# Bus-switch.net
KiCad netlist of a schematic drawn in Altium Designer
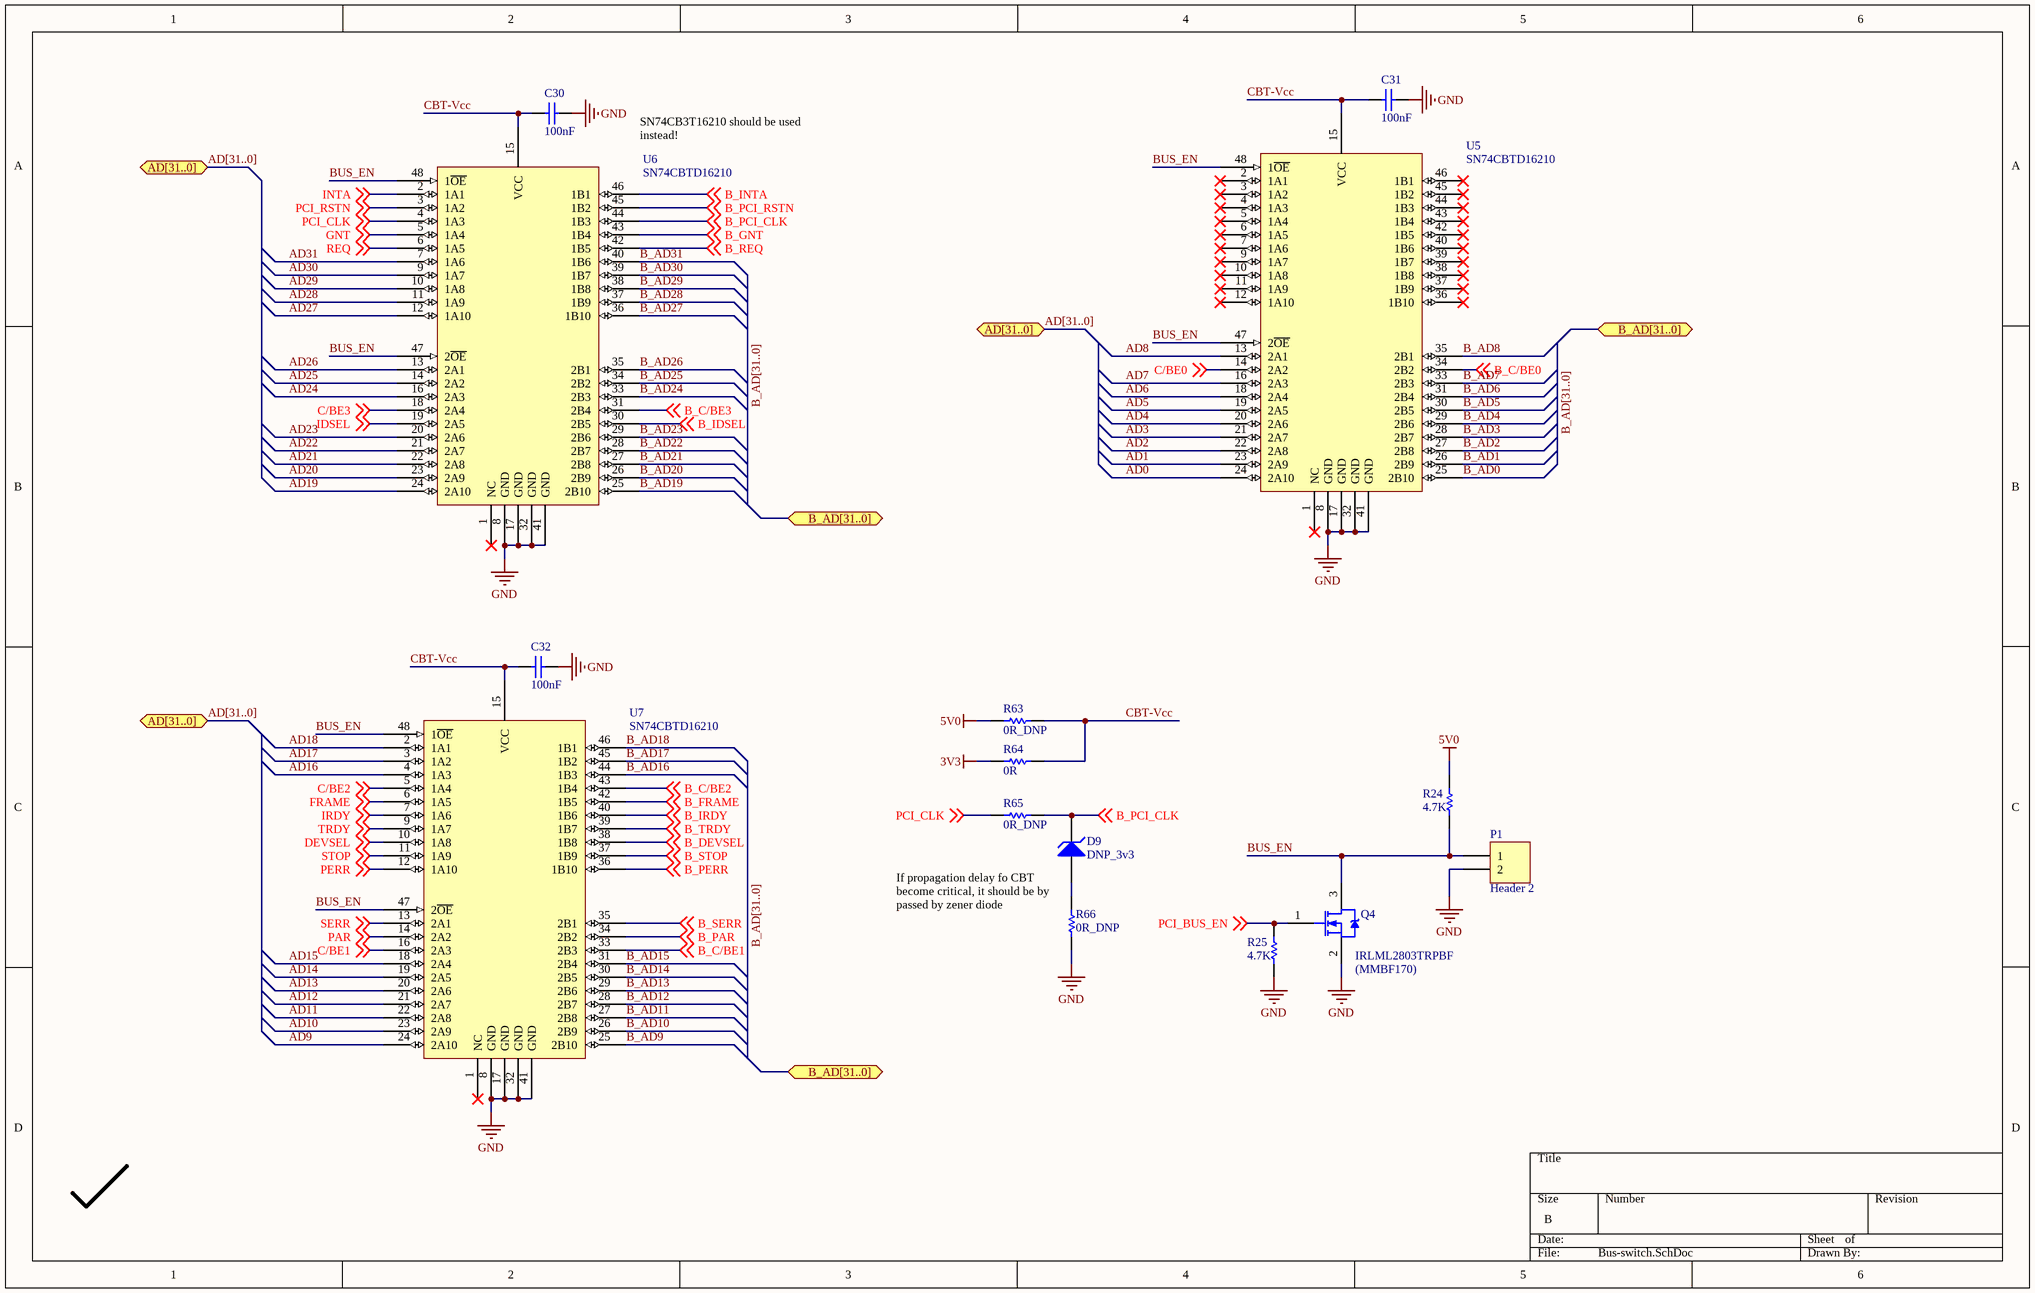
[diagram p0: Bus-switch.SchDoc]

(export (version "E")
  (design (tool "Eeschema 10.0.6"))
  (components
    (comp (ref "C30")
      (value "100nF")
      (footprint "0603PKG")
      (description "Capacitor (Semiconductor SIM Model)")
      (fields (field (name "Comment") "Cap Semi") (field (name "PUBLISHER") "Altium Limited"))
      (libsource (lib "Miscellaneous Devices") (part "Cap Semi"))
    )
    (comp (ref "C31")
      (value "100nF")
      (footprint "0603PKG")
      (description "Capacitor (Semiconductor SIM Model)")
      (fields (field (name "Comment") "Cap Semi") (field (name "PUBLISHER") "Altium Limited"))
      (libsource (lib "Miscellaneous Devices") (part "Cap Semi"))
    )
    (comp (ref "C32")
      (value "100nF")
      (footprint "0603PKG")
      (description "Capacitor (Semiconductor SIM Model)")
      (fields (field (name "Comment") "Cap Semi") (field (name "PUBLISHER") "Altium Limited"))
      (libsource (lib "Miscellaneous Devices") (part "Cap Semi"))
    )
    (comp (ref "D9")
      (value "DNP_3v3")
      (footprint "C1206")
      (description "Zener Diode")
      (fields (field (name "PUBLISHER") "Altium Limited"))
      (libsource (lib "Miscellaneous Devices") (part "D Zener"))
    )
    (comp (ref "P1")
      (value "Header 2")
      (footprint "HDR1X2")
      (description "Header, 2-Pin")
      (fields (field (name "PUBLISHER") "Altium Limited"))
      (libsource (lib "Miscellaneous Connectors") (part "Header 2"))
    )
    (comp (ref "Q4")
      (value "IRLML2803TRPBF")
      (footprint "SOT23")
      (description "N-Channel Power MOSFET")
      (fields (field (name "PUBLISHER") "Altium Limited"))
      (libsource (lib "Miscellaneous Devices") (part "NMOS-2"))
    )
    (comp (ref "R24")
      (value "4.7K")
      (footprint "0603PKG")
      (description "Resistor")
      (fields (field (name "Comment") "Res1") (field (name "PUBLISHER") "Altium Limited"))
      (libsource (lib "Miscellaneous Devices") (part "Res1"))
    )
    (comp (ref "R25")
      (value "4.7K")
      (footprint "0603PKG")
      (description "Resistor")
      (fields (field (name "Comment") "Res1") (field (name "PUBLISHER") "Altium Limited"))
      (libsource (lib "Miscellaneous Devices") (part "Res1"))
    )
    (comp (ref "R63")
      (value "0R_DNP")
      (footprint "0603PKG")
      (description "Resistor")
      (fields (field (name "Comment") "Res1") (field (name "PUBLISHER") "Altium Limited"))
      (libsource (lib "Miscellaneous Devices") (part "Res1"))
    )
    (comp (ref "R64")
      (value "0R")
      (footprint "0603PKG")
      (description "Resistor")
      (fields (field (name "Comment") "Res1") (field (name "PUBLISHER") "Altium Limited"))
      (libsource (lib "Miscellaneous Devices") (part "Res1"))
    )
    (comp (ref "R65")
      (value "0R_DNP")
      (footprint "0603PKG")
      (description "Resistor")
      (fields (field (name "Comment") "Res1") (field (name "PUBLISHER") "Altium Limited"))
      (libsource (lib "Miscellaneous Devices") (part "Res1"))
    )
    (comp (ref "R66")
      (value "0R_DNP")
      (footprint "0603PKG")
      (description "Resistor")
      (fields (field (name "Comment") "Res1") (field (name "PUBLISHER") "Altium Limited"))
      (libsource (lib "Miscellaneous Devices") (part "Res1"))
    )
    (comp (ref "U5")
      (value "SN74CBTD16210")
      (footprint "TSSOP-48-DGG")
      (description "20-BIT FET BUS SWITCH WITH LEVEL SHIFTING")
      (libsource (lib "Conn_Schlib") (part "SN74CBTD16210"))
    )
    (comp (ref "U6")
      (value "SN74CBTD16210")
      (footprint "TSSOP-48-DGG")
      (description "20-BIT FET BUS SWITCH WITH LEVEL SHIFTING")
      (libsource (lib "Conn_Schlib") (part "SN74CBTD16210"))
    )
    (comp (ref "U7")
      (value "SN74CBTD16210")
      (footprint "TSSOP-48-DGG")
      (description "20-BIT FET BUS SWITCH WITH LEVEL SHIFTING")
      (libsource (lib "Conn_Schlib") (part "SN74CBTD16210"))
    )
  )
  (nets
    (net (code "1") (name "/AD0") (class "Default")
      (node (ref "U5") (pin "24") (pinfunction "2A10_24") (pintype "bidirectional"))
    )
    (net (code "2") (name "/AD1") (class "Default")
      (node (ref "U5") (pin "23") (pinfunction "2A9_23") (pintype "bidirectional"))
    )
    (net (code "3") (name "/AD2") (class "Default")
      (node (ref "U5") (pin "22") (pinfunction "2A8_22") (pintype "bidirectional"))
    )
    (net (code "4") (name "/AD3") (class "Default")
      (node (ref "U5") (pin "21") (pinfunction "2A7_21") (pintype "bidirectional"))
    )
    (net (code "5") (name "/AD4") (class "Default")
      (node (ref "U5") (pin "20") (pinfunction "2A6_20") (pintype "bidirectional"))
    )
    (net (code "6") (name "/AD5") (class "Default")
      (node (ref "U5") (pin "19") (pinfunction "2A5_19") (pintype "bidirectional"))
    )
    (net (code "7") (name "/AD6") (class "Default")
      (node (ref "U5") (pin "18") (pinfunction "2A4_18") (pintype "bidirectional"))
    )
    (net (code "8") (name "/AD7") (class "Default")
      (node (ref "U5") (pin "16") (pinfunction "2A3_16") (pintype "bidirectional"))
    )
    (net (code "9") (name "/AD8") (class "Default")
      (node (ref "U5") (pin "13") (pinfunction "2A1_13") (pintype "bidirectional"))
    )
    (net (code "10") (name "/AD9") (class "Default")
      (node (ref "U7") (pin "24") (pinfunction "2A10_24") (pintype "bidirectional"))
    )
    (net (code "11") (name "/AD10") (class "Default")
      (node (ref "U7") (pin "23") (pinfunction "2A9_23") (pintype "bidirectional"))
    )
    (net (code "12") (name "/AD11") (class "Default")
      (node (ref "U7") (pin "22") (pinfunction "2A8_22") (pintype "bidirectional"))
    )
    (net (code "13") (name "/AD12") (class "Default")
      (node (ref "U7") (pin "21") (pinfunction "2A7_21") (pintype "bidirectional"))
    )
    (net (code "14") (name "/AD13") (class "Default")
      (node (ref "U7") (pin "20") (pinfunction "2A6_20") (pintype "bidirectional"))
    )
    (net (code "15") (name "/AD14") (class "Default")
      (node (ref "U7") (pin "19") (pinfunction "2A5_19") (pintype "bidirectional"))
    )
    (net (code "16") (name "/AD15") (class "Default")
      (node (ref "U7") (pin "18") (pinfunction "2A4_18") (pintype "bidirectional"))
    )
    (net (code "17") (name "/AD16") (class "Default")
      (node (ref "U7") (pin "4") (pinfunction "1A3_4") (pintype "bidirectional"))
    )
    (net (code "18") (name "/AD17") (class "Default")
      (node (ref "U7") (pin "3") (pinfunction "1A2_3") (pintype "bidirectional"))
    )
    (net (code "19") (name "/AD18") (class "Default")
      (node (ref "U7") (pin "2") (pinfunction "1A1_2") (pintype "bidirectional"))
    )
    (net (code "20") (name "/AD19") (class "Default")
      (node (ref "U6") (pin "24") (pinfunction "2A10_24") (pintype "bidirectional"))
    )
    (net (code "21") (name "/AD20") (class "Default")
      (node (ref "U6") (pin "23") (pinfunction "2A9_23") (pintype "bidirectional"))
    )
    (net (code "22") (name "/AD21") (class "Default")
      (node (ref "U6") (pin "22") (pinfunction "2A8_22") (pintype "bidirectional"))
    )
    (net (code "23") (name "/AD22") (class "Default")
      (node (ref "U6") (pin "21") (pinfunction "2A7_21") (pintype "bidirectional"))
    )
    (net (code "24") (name "/AD23") (class "Default")
      (node (ref "U6") (pin "20") (pinfunction "2A6_20") (pintype "bidirectional"))
    )
    (net (code "25") (name "/AD24") (class "Default")
      (node (ref "U6") (pin "16") (pinfunction "2A3_16") (pintype "bidirectional"))
    )
    (net (code "26") (name "/AD25") (class "Default")
      (node (ref "U6") (pin "14") (pinfunction "2A2_14") (pintype "bidirectional"))
    )
    (net (code "27") (name "/AD26") (class "Default")
      (node (ref "U6") (pin "13") (pinfunction "2A1_13") (pintype "bidirectional"))
    )
    (net (code "28") (name "/AD27") (class "Default")
      (node (ref "U6") (pin "12") (pinfunction "1A10_12") (pintype "bidirectional"))
    )
    (net (code "29") (name "/AD28") (class "Default")
      (node (ref "U6") (pin "11") (pinfunction "1A9_11") (pintype "bidirectional"))
    )
    (net (code "30") (name "/AD29") (class "Default")
      (node (ref "U6") (pin "10") (pinfunction "1A8_10") (pintype "bidirectional"))
    )
    (net (code "31") (name "/AD30") (class "Default")
      (node (ref "U6") (pin "9") (pinfunction "1A7_9") (pintype "bidirectional"))
    )
    (net (code "32") (name "/AD31") (class "Default")
      (node (ref "U6") (pin "7") (pinfunction "1A6_7") (pintype "bidirectional"))
    )
    (net (code "34") (name "/BUS_EN") (class "Default")
      (node (ref "P1") (pin "1") (pinfunction "1_1") (pintype "passive"))
      (node (ref "Q4") (pin "3") (pinfunction "D_3") (pintype "passive"))
      (node (ref "R24") (pin "1") (pinfunction "1_1") (pintype "passive"))
      (node (ref "U5") (pin "47") (pinfunction "2~{OE}_47") (pintype "input"))
      (node (ref "U5") (pin "48") (pinfunction "1~{OE}_48") (pintype "input"))
      (node (ref "U6") (pin "47") (pinfunction "2~{OE}_47") (pintype "input"))
      (node (ref "U6") (pin "48") (pinfunction "1~{OE}_48") (pintype "input"))
      (node (ref "U7") (pin "47") (pinfunction "2~{OE}_47") (pintype "input"))
      (node (ref "U7") (pin "48") (pinfunction "1~{OE}_48") (pintype "input"))
    )
    (net (code "35") (name "/B_AD0") (class "Default")
      (node (ref "U5") (pin "25") (pinfunction "2B10_25") (pintype "bidirectional"))
    )
    (net (code "36") (name "/B_AD1") (class "Default")
      (node (ref "U5") (pin "26") (pinfunction "2B9_26") (pintype "bidirectional"))
    )
    (net (code "37") (name "/B_AD2") (class "Default")
      (node (ref "U5") (pin "27") (pinfunction "2B8_27") (pintype "bidirectional"))
    )
    (net (code "38") (name "/B_AD3") (class "Default")
      (node (ref "U5") (pin "28") (pinfunction "2B7_28") (pintype "bidirectional"))
    )
    (net (code "39") (name "/B_AD4") (class "Default")
      (node (ref "U5") (pin "29") (pinfunction "2B6_29") (pintype "bidirectional"))
    )
    (net (code "40") (name "/B_AD5") (class "Default")
      (node (ref "U5") (pin "30") (pinfunction "2B5_30") (pintype "bidirectional"))
    )
    (net (code "41") (name "/B_AD6") (class "Default")
      (node (ref "U5") (pin "31") (pinfunction "2B4_31") (pintype "bidirectional"))
    )
    (net (code "42") (name "/B_AD7") (class "Default")
      (node (ref "U5") (pin "33") (pinfunction "2B3_33") (pintype "bidirectional"))
    )
    (net (code "43") (name "/B_AD8") (class "Default")
      (node (ref "U5") (pin "35") (pinfunction "2B1_35") (pintype "bidirectional"))
    )
    (net (code "44") (name "/B_AD9") (class "Default")
      (node (ref "U7") (pin "25") (pinfunction "2B10_25") (pintype "bidirectional"))
    )
    (net (code "45") (name "/B_AD10") (class "Default")
      (node (ref "U7") (pin "26") (pinfunction "2B9_26") (pintype "bidirectional"))
    )
    (net (code "46") (name "/B_AD11") (class "Default")
      (node (ref "U7") (pin "27") (pinfunction "2B8_27") (pintype "bidirectional"))
    )
    (net (code "47") (name "/B_AD12") (class "Default")
      (node (ref "U7") (pin "28") (pinfunction "2B7_28") (pintype "bidirectional"))
    )
    (net (code "48") (name "/B_AD13") (class "Default")
      (node (ref "U7") (pin "29") (pinfunction "2B6_29") (pintype "bidirectional"))
    )
    (net (code "49") (name "/B_AD14") (class "Default")
      (node (ref "U7") (pin "30") (pinfunction "2B5_30") (pintype "bidirectional"))
    )
    (net (code "50") (name "/B_AD15") (class "Default")
      (node (ref "U7") (pin "31") (pinfunction "2B4_31") (pintype "bidirectional"))
    )
    (net (code "51") (name "/B_AD16") (class "Default")
      (node (ref "U7") (pin "44") (pinfunction "1B3_44") (pintype "bidirectional"))
    )
    (net (code "52") (name "/B_AD17") (class "Default")
      (node (ref "U7") (pin "45") (pinfunction "1B2_45") (pintype "bidirectional"))
    )
    (net (code "53") (name "/B_AD18") (class "Default")
      (node (ref "U7") (pin "46") (pinfunction "1B1_46") (pintype "bidirectional"))
    )
    (net (code "54") (name "/B_AD19") (class "Default")
      (node (ref "U6") (pin "25") (pinfunction "2B10_25") (pintype "bidirectional"))
    )
    (net (code "55") (name "/B_AD20") (class "Default")
      (node (ref "U6") (pin "26") (pinfunction "2B9_26") (pintype "bidirectional"))
    )
    (net (code "56") (name "/B_AD21") (class "Default")
      (node (ref "U6") (pin "27") (pinfunction "2B8_27") (pintype "bidirectional"))
    )
    (net (code "57") (name "/B_AD22") (class "Default")
      (node (ref "U6") (pin "28") (pinfunction "2B7_28") (pintype "bidirectional"))
    )
    (net (code "58") (name "/B_AD23") (class "Default")
      (node (ref "U6") (pin "29") (pinfunction "2B6_29") (pintype "bidirectional"))
    )
    (net (code "59") (name "/B_AD24") (class "Default")
      (node (ref "U6") (pin "33") (pinfunction "2B3_33") (pintype "bidirectional"))
    )
    (net (code "60") (name "/B_AD25") (class "Default")
      (node (ref "U6") (pin "34") (pinfunction "2B2_34") (pintype "bidirectional"))
    )
    (net (code "61") (name "/B_AD26") (class "Default")
      (node (ref "U6") (pin "35") (pinfunction "2B1_35") (pintype "bidirectional"))
    )
    (net (code "62") (name "/B_AD27") (class "Default")
      (node (ref "U6") (pin "36") (pinfunction "1B10_36") (pintype "bidirectional"))
    )
    (net (code "63") (name "/B_AD28") (class "Default")
      (node (ref "U6") (pin "37") (pinfunction "1B9_37") (pintype "bidirectional"))
    )
    (net (code "64") (name "/B_AD29") (class "Default")
      (node (ref "U6") (pin "38") (pinfunction "1B8_38") (pintype "bidirectional"))
    )
    (net (code "65") (name "/B_AD30") (class "Default")
      (node (ref "U6") (pin "39") (pinfunction "1B7_39") (pintype "bidirectional"))
    )
    (net (code "66") (name "/B_AD31") (class "Default")
      (node (ref "U6") (pin "40") (pinfunction "1B6_40") (pintype "bidirectional"))
    )
    (net (code "68") (name "/CBT-Vcc") (class "Default")
      (node (ref "C30") (pin "2") (pinfunction "2_2") (pintype "passive"))
      (node (ref "C31") (pin "2") (pinfunction "2_2") (pintype "passive"))
      (node (ref "C32") (pin "2") (pinfunction "2_2") (pintype "passive"))
      (node (ref "R63") (pin "1") (pinfunction "1_1") (pintype "passive"))
      (node (ref "R64") (pin "1") (pinfunction "1_1") (pintype "passive"))
      (node (ref "U5") (pin "15") (pinfunction "VCC_15") (pintype "power_in"))
      (node (ref "U6") (pin "15") (pinfunction "VCC_15") (pintype "power_in"))
      (node (ref "U7") (pin "15") (pinfunction "VCC_15") (pintype "power_in"))
    )
    (net (code "69") (name "3V3") (class "Default")
      (node (ref "R64") (pin "2") (pinfunction "2_2") (pintype "passive"))
    )
    (net (code "70") (name "5V0") (class "Default")
      (node (ref "R24") (pin "2") (pinfunction "2_2") (pintype "passive"))
      (node (ref "R63") (pin "2") (pinfunction "2_2") (pintype "passive"))
    )
    (net (code "71") (name "B_C{slash}BE0") (class "Default")
      (node (ref "U5") (pin "34") (pinfunction "2B2_34") (pintype "bidirectional"))
    )
    (net (code "72") (name "B_C{slash}BE1") (class "Default")
      (node (ref "U7") (pin "33") (pinfunction "2B3_33") (pintype "bidirectional"))
    )
    (net (code "73") (name "B_C{slash}BE2") (class "Default")
      (node (ref "U7") (pin "43") (pinfunction "1B4_43") (pintype "bidirectional"))
    )
    (net (code "74") (name "B_C{slash}BE3") (class "Default")
      (node (ref "U6") (pin "31") (pinfunction "2B4_31") (pintype "bidirectional"))
    )
    (net (code "75") (name "B_DEVSEL") (class "Default")
      (node (ref "U7") (pin "38") (pinfunction "1B8_38") (pintype "bidirectional"))
    )
    (net (code "76") (name "B_FRAME") (class "Default")
      (node (ref "U7") (pin "42") (pinfunction "1B5_42") (pintype "bidirectional"))
    )
    (net (code "77") (name "B_GNT") (class "Default")
      (node (ref "U6") (pin "43") (pinfunction "1B4_43") (pintype "bidirectional"))
    )
    (net (code "78") (name "B_IDSEL") (class "Default")
      (node (ref "U6") (pin "30") (pinfunction "2B5_30") (pintype "bidirectional"))
    )
    (net (code "79") (name "B_INTA") (class "Default")
      (node (ref "U6") (pin "46") (pinfunction "1B1_46") (pintype "bidirectional"))
    )
    (net (code "80") (name "B_IRDY") (class "Default")
      (node (ref "U7") (pin "40") (pinfunction "1B6_40") (pintype "bidirectional"))
    )
    (net (code "81") (name "B_PAR") (class "Default")
      (node (ref "U7") (pin "34") (pinfunction "2B2_34") (pintype "bidirectional"))
    )
    (net (code "82") (name "B_PCI_CLK") (class "Default")
      (node (ref "D9") (pin "2") (pinfunction "K_2") (pintype "passive"))
      (node (ref "R65") (pin "1") (pinfunction "1_1") (pintype "passive"))
      (node (ref "U6") (pin "44") (pinfunction "1B3_44") (pintype "bidirectional"))
    )
    (net (code "83") (name "B_PCI_RSTN") (class "Default")
      (node (ref "U6") (pin "45") (pinfunction "1B2_45") (pintype "bidirectional"))
    )
    (net (code "84") (name "B_PERR") (class "Default")
      (node (ref "U7") (pin "36") (pinfunction "1B10_36") (pintype "bidirectional"))
    )
    (net (code "85") (name "B_REQ") (class "Default")
      (node (ref "U6") (pin "42") (pinfunction "1B5_42") (pintype "bidirectional"))
    )
    (net (code "86") (name "B_SERR") (class "Default")
      (node (ref "U7") (pin "35") (pinfunction "2B1_35") (pintype "bidirectional"))
    )
    (net (code "87") (name "B_STOP") (class "Default")
      (node (ref "U7") (pin "37") (pinfunction "1B9_37") (pintype "bidirectional"))
    )
    (net (code "88") (name "B_TRDY") (class "Default")
      (node (ref "U7") (pin "39") (pinfunction "1B7_39") (pintype "bidirectional"))
    )
    (net (code "89") (name "C{slash}BE0") (class "Default")
      (node (ref "U5") (pin "14") (pinfunction "2A2_14") (pintype "bidirectional"))
    )
    (net (code "90") (name "C{slash}BE1") (class "Default")
      (node (ref "U7") (pin "16") (pinfunction "2A3_16") (pintype "bidirectional"))
    )
    (net (code "91") (name "C{slash}BE2") (class "Default")
      (node (ref "U7") (pin "5") (pinfunction "1A4_5") (pintype "bidirectional"))
    )
    (net (code "92") (name "C{slash}BE3") (class "Default")
      (node (ref "U6") (pin "18") (pinfunction "2A4_18") (pintype "bidirectional"))
    )
    (net (code "93") (name "DEVSEL") (class "Default")
      (node (ref "U7") (pin "10") (pinfunction "1A8_10") (pintype "bidirectional"))
    )
    (net (code "94") (name "FRAME") (class "Default")
      (node (ref "U7") (pin "6") (pinfunction "1A5_6") (pintype "bidirectional"))
    )
    (net (code "95") (name "GND") (class "Default")
      (node (ref "C30") (pin "1") (pinfunction "1_1") (pintype "passive"))
      (node (ref "C31") (pin "1") (pinfunction "1_1") (pintype "passive"))
      (node (ref "C32") (pin "1") (pinfunction "1_1") (pintype "passive"))
      (node (ref "P1") (pin "2") (pinfunction "2_2") (pintype "passive"))
      (node (ref "Q4") (pin "2") (pinfunction "S_2") (pintype "passive"))
      (node (ref "R25") (pin "1") (pinfunction "1_1") (pintype "passive"))
      (node (ref "R66") (pin "2") (pinfunction "2_2") (pintype "passive"))
      (node (ref "U5") (pin "17") (pinfunction "GND_17") (pintype "power_in"))
      (node (ref "U5") (pin "32") (pinfunction "GND_32") (pintype "power_in"))
      (node (ref "U5") (pin "41") (pinfunction "GND_41") (pintype "power_in"))
      (node (ref "U5") (pin "8") (pinfunction "GND_8") (pintype "power_in"))
      (node (ref "U6") (pin "17") (pinfunction "GND_17") (pintype "power_in"))
      (node (ref "U6") (pin "32") (pinfunction "GND_32") (pintype "power_in"))
      (node (ref "U6") (pin "41") (pinfunction "GND_41") (pintype "power_in"))
      (node (ref "U6") (pin "8") (pinfunction "GND_8") (pintype "power_in"))
      (node (ref "U7") (pin "17") (pinfunction "GND_17") (pintype "power_in"))
      (node (ref "U7") (pin "32") (pinfunction "GND_32") (pintype "power_in"))
      (node (ref "U7") (pin "41") (pinfunction "GND_41") (pintype "power_in"))
      (node (ref "U7") (pin "8") (pinfunction "GND_8") (pintype "power_in"))
    )
    (net (code "96") (name "GNT") (class "Default")
      (node (ref "U6") (pin "5") (pinfunction "1A4_5") (pintype "bidirectional"))
    )
    (net (code "97") (name "IDSEL") (class "Default")
      (node (ref "U6") (pin "19") (pinfunction "2A5_19") (pintype "bidirectional"))
    )
    (net (code "98") (name "INTA") (class "Default")
      (node (ref "U6") (pin "2") (pinfunction "1A1_2") (pintype "bidirectional"))
    )
    (net (code "99") (name "IRDY") (class "Default")
      (node (ref "U7") (pin "7") (pinfunction "1A6_7") (pintype "bidirectional"))
    )
    (net (code "100") (name "Net-(D9-A)") (class "Default")
      (node (ref "D9") (pin "1") (pinfunction "A_1") (pintype "passive"))
      (node (ref "R66") (pin "1") (pinfunction "1_1") (pintype "passive"))
    )
    (net (code "101") (name "PAR") (class "Default")
      (node (ref "U7") (pin "14") (pinfunction "2A2_14") (pintype "bidirectional"))
    )
    (net (code "102") (name "PCI_BUS_EN") (class "Default")
      (node (ref "Q4") (pin "1") (pinfunction "G_1") (pintype "passive"))
      (node (ref "R25") (pin "2") (pinfunction "2_2") (pintype "passive"))
    )
    (net (code "103") (name "PCI_CLK") (class "Default")
      (node (ref "R65") (pin "2") (pinfunction "2_2") (pintype "passive"))
      (node (ref "U6") (pin "4") (pinfunction "1A3_4") (pintype "bidirectional"))
    )
    (net (code "104") (name "PCI_RSTN") (class "Default")
      (node (ref "U6") (pin "3") (pinfunction "1A2_3") (pintype "bidirectional"))
    )
    (net (code "105") (name "PERR") (class "Default")
      (node (ref "U7") (pin "12") (pinfunction "1A10_12") (pintype "bidirectional"))
    )
    (net (code "106") (name "REQ") (class "Default")
      (node (ref "U6") (pin "6") (pinfunction "1A5_6") (pintype "bidirectional"))
    )
    (net (code "107") (name "SERR") (class "Default")
      (node (ref "U7") (pin "13") (pinfunction "2A1_13") (pintype "bidirectional"))
    )
    (net (code "108") (name "STOP") (class "Default")
      (node (ref "U7") (pin "11") (pinfunction "1A9_11") (pintype "bidirectional"))
    )
    (net (code "109") (name "TRDY") (class "Default")
      (node (ref "U7") (pin "9") (pinfunction "1A7_9") (pintype "bidirectional"))
    )
    (net (code "110") (name "unconnected-(U5-1A1-Pad2)") (class "Default")
      (node (ref "U5") (pin "2") (pinfunction "1A1_2") (pintype "bidirectional+no_connect"))
    )
    (net (code "111") (name "unconnected-(U5-1A2-Pad3)") (class "Default")
      (node (ref "U5") (pin "3") (pinfunction "1A2_3") (pintype "bidirectional+no_connect"))
    )
    (net (code "112") (name "unconnected-(U5-1A3-Pad4)") (class "Default")
      (node (ref "U5") (pin "4") (pinfunction "1A3_4") (pintype "bidirectional+no_connect"))
    )
    (net (code "113") (name "unconnected-(U5-1A4-Pad5)") (class "Default")
      (node (ref "U5") (pin "5") (pinfunction "1A4_5") (pintype "bidirectional+no_connect"))
    )
    (net (code "114") (name "unconnected-(U5-1A5-Pad6)") (class "Default")
      (node (ref "U5") (pin "6") (pinfunction "1A5_6") (pintype "bidirectional+no_connect"))
    )
    (net (code "115") (name "unconnected-(U5-1A6-Pad7)") (class "Default")
      (node (ref "U5") (pin "7") (pinfunction "1A6_7") (pintype "bidirectional+no_connect"))
    )
    (net (code "116") (name "unconnected-(U5-1A7-Pad9)") (class "Default")
      (node (ref "U5") (pin "9") (pinfunction "1A7_9") (pintype "bidirectional+no_connect"))
    )
    (net (code "117") (name "unconnected-(U5-1A8-Pad10)") (class "Default")
      (node (ref "U5") (pin "10") (pinfunction "1A8_10") (pintype "bidirectional+no_connect"))
    )
    (net (code "118") (name "unconnected-(U5-1A9-Pad11)") (class "Default")
      (node (ref "U5") (pin "11") (pinfunction "1A9_11") (pintype "bidirectional+no_connect"))
    )
    (net (code "119") (name "unconnected-(U5-1A10-Pad12)") (class "Default")
      (node (ref "U5") (pin "12") (pinfunction "1A10_12") (pintype "bidirectional+no_connect"))
    )
    (net (code "120") (name "unconnected-(U5-1B1-Pad46)") (class "Default")
      (node (ref "U5") (pin "46") (pinfunction "1B1_46") (pintype "bidirectional+no_connect"))
    )
    (net (code "121") (name "unconnected-(U5-1B2-Pad45)") (class "Default")
      (node (ref "U5") (pin "45") (pinfunction "1B2_45") (pintype "bidirectional+no_connect"))
    )
    (net (code "122") (name "unconnected-(U5-1B3-Pad44)") (class "Default")
      (node (ref "U5") (pin "44") (pinfunction "1B3_44") (pintype "bidirectional+no_connect"))
    )
    (net (code "123") (name "unconnected-(U5-1B4-Pad43)") (class "Default")
      (node (ref "U5") (pin "43") (pinfunction "1B4_43") (pintype "bidirectional+no_connect"))
    )
    (net (code "124") (name "unconnected-(U5-1B5-Pad42)") (class "Default")
      (node (ref "U5") (pin "42") (pinfunction "1B5_42") (pintype "bidirectional+no_connect"))
    )
    (net (code "125") (name "unconnected-(U5-1B6-Pad40)") (class "Default")
      (node (ref "U5") (pin "40") (pinfunction "1B6_40") (pintype "bidirectional+no_connect"))
    )
    (net (code "126") (name "unconnected-(U5-1B7-Pad39)") (class "Default")
      (node (ref "U5") (pin "39") (pinfunction "1B7_39") (pintype "bidirectional+no_connect"))
    )
    (net (code "127") (name "unconnected-(U5-1B8-Pad38)") (class "Default")
      (node (ref "U5") (pin "38") (pinfunction "1B8_38") (pintype "bidirectional+no_connect"))
    )
    (net (code "128") (name "unconnected-(U5-1B9-Pad37)") (class "Default")
      (node (ref "U5") (pin "37") (pinfunction "1B9_37") (pintype "bidirectional+no_connect"))
    )
    (net (code "129") (name "unconnected-(U5-1B10-Pad36)") (class "Default")
      (node (ref "U5") (pin "36") (pinfunction "1B10_36") (pintype "bidirectional+no_connect"))
    )
    (net (code "130") (name "unconnected-(U5-NC-Pad1)") (class "Default")
      (node (ref "U5") (pin "1") (pinfunction "NC_1") (pintype "passive+no_connect"))
    )
    (net (code "131") (name "unconnected-(U6-NC-Pad1)") (class "Default")
      (node (ref "U6") (pin "1") (pinfunction "NC_1") (pintype "passive+no_connect"))
    )
    (net (code "132") (name "unconnected-(U7-NC-Pad1)") (class "Default")
      (node (ref "U7") (pin "1") (pinfunction "NC_1") (pintype "passive+no_connect"))
    )
  )
)
